# VCU-S02-V00-12VProtection.net
KiCad netlist of a schematic drawn in Altium Designer
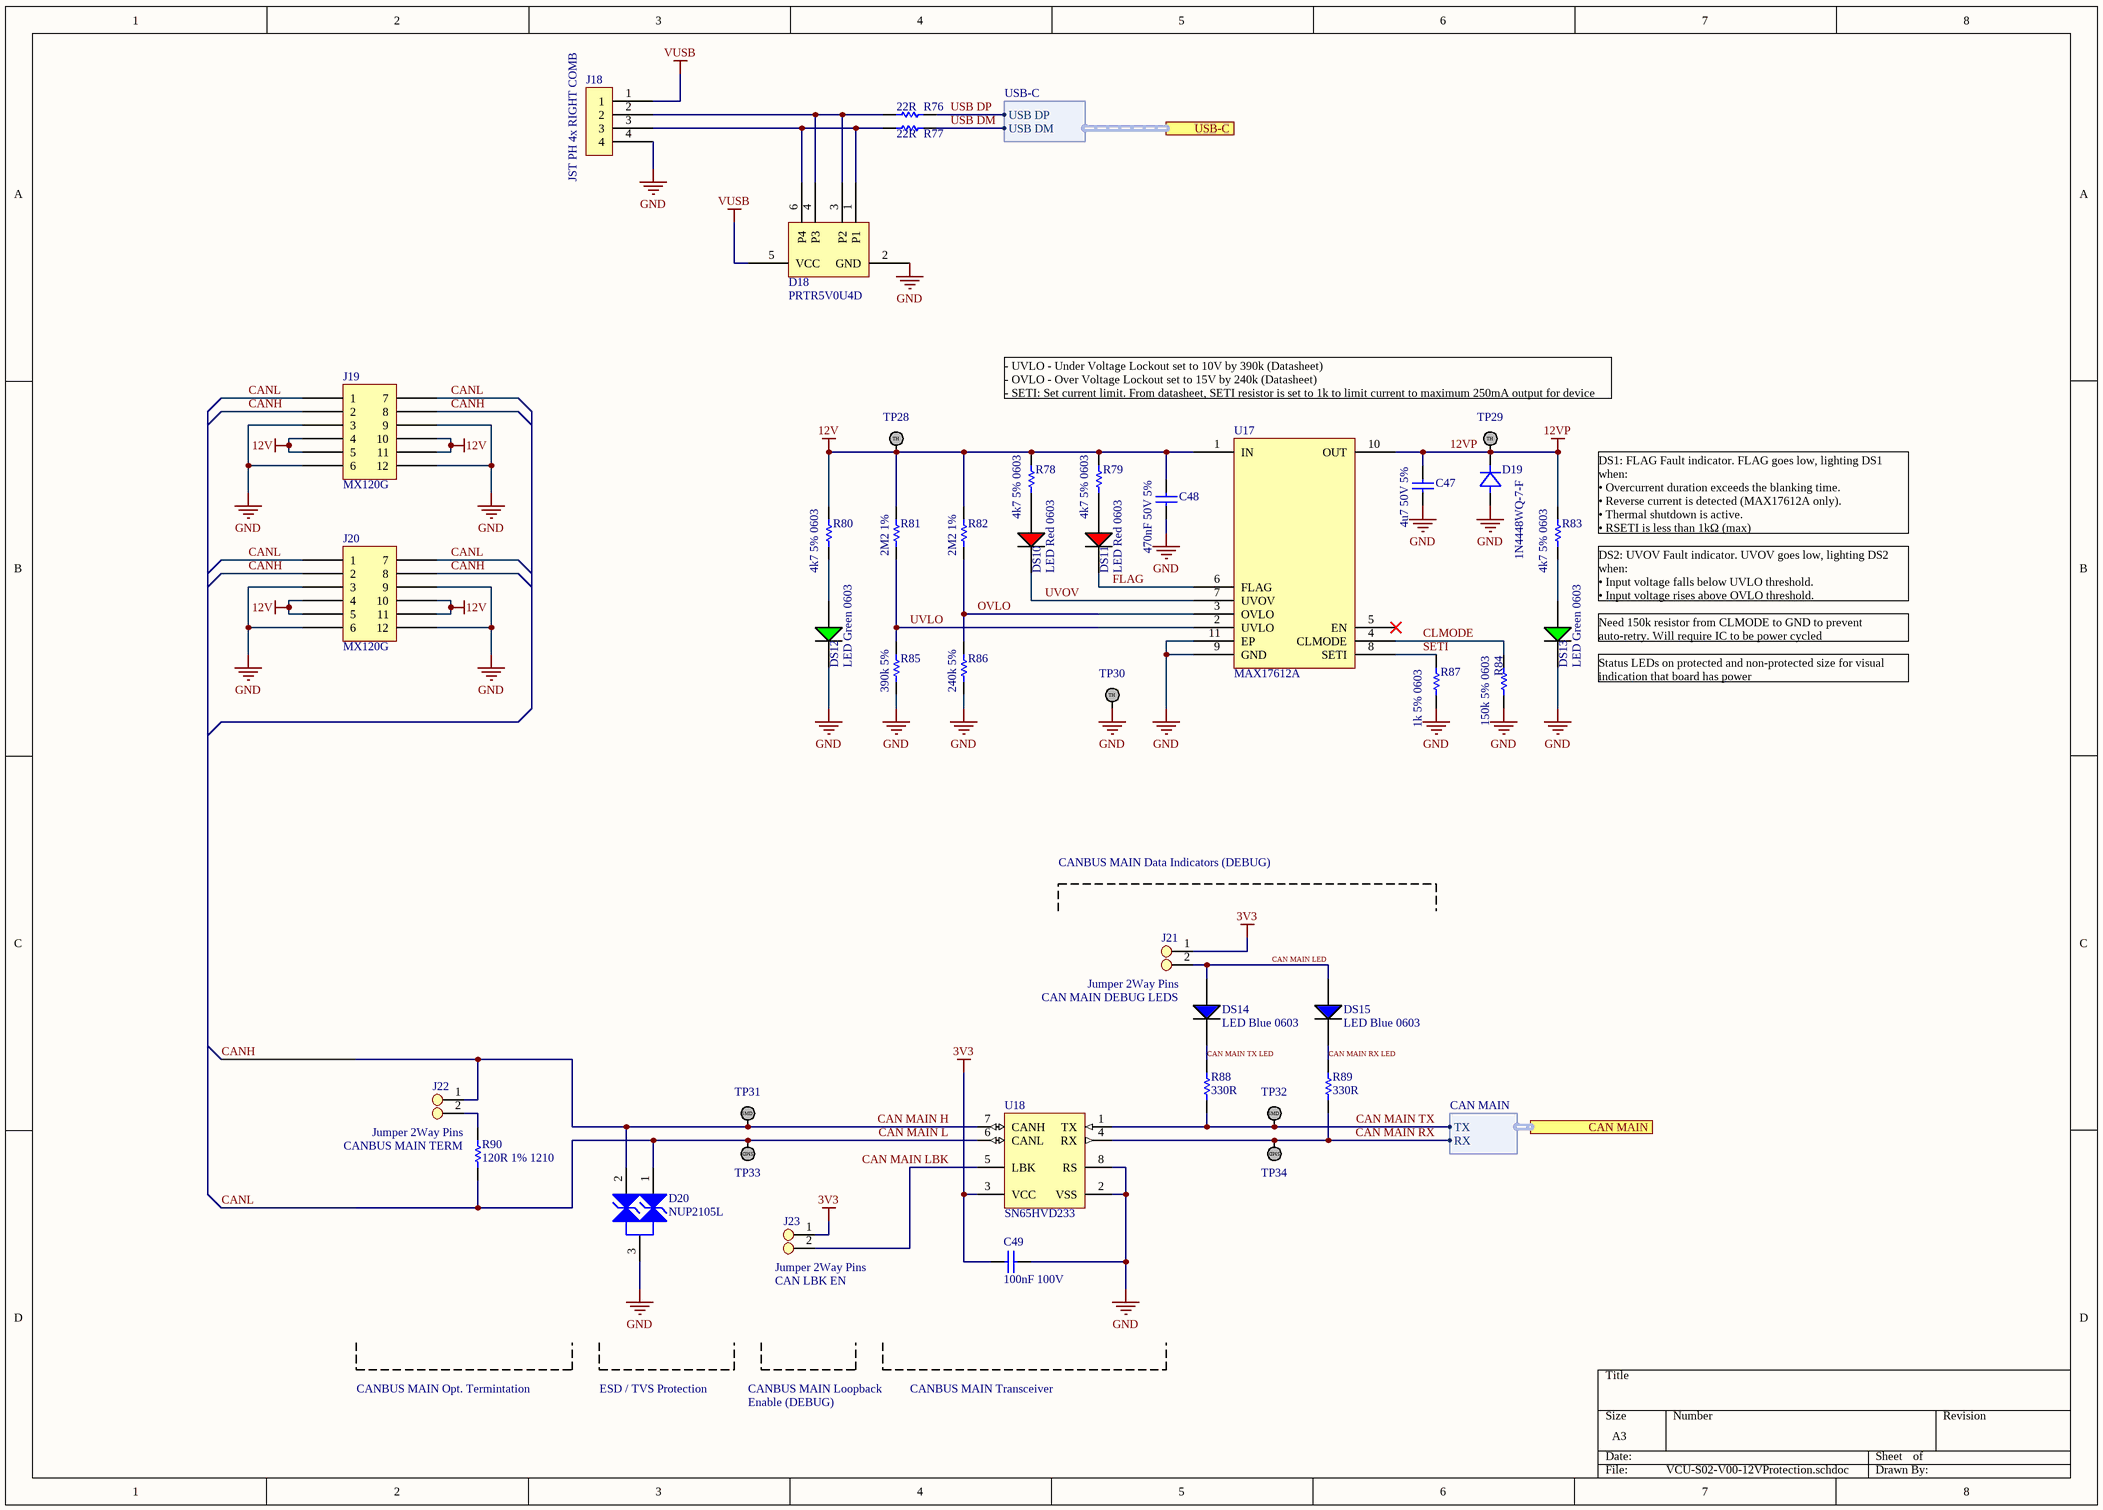
[diagram p0: VCU-S02-V00-12VProtection.schdoc]

(export (version "E")
  (design (tool "Eeschema 10.0.6"))
  (components
    (comp (ref "C47")
      (value "4u7 50V 5%")
      (footprint "Cap_Ceramic_0603")
      (description "Capacitor, Ceramic, SMD, 4u7, 50V, 5%, X7R, 0603")
      (libsource (lib "StandardCapacitors") (part "4u7 50V 5% X7R 0603"))
    )
    (comp (ref "C48")
      (value "470nF 50V 5%")
      (footprint "Cap_Ceramic_0603")
      (description "Capacitor, Ceramic, SMD, 470nF, 50V, 5%, X7R, 0603")
      (libsource (lib "StandardCapacitors") (part "470nF 50V 5% X7R 0603"))
    )
    (comp (ref "C49")
      (value "100nF 100V")
      (footprint "Cap_Ceramic_0603")
      (description "Capacitor, Ceramic, SMD, 100nF, 100V, 5%, X7R, 0603")
      (libsource (lib "StandardCapacitors") (part "100nF 100V 5% X7R 0603"))
    )
    (comp (ref "D18")
      (value "PRTR5V0U4D")
      (footprint "SC-47")
      (description "Clamp Ipp Tvs Diode Surface Mount 6-TSOP")
      (libsource (lib "QUTMS-MCISOLibrary") (part "PRTR5V0U4D"))
    )
    (comp (ref "D19")
      (value "1N4448WQ-7-F")
      (footprint "SMA")
      (description "Diode, SMD, 75V, 5%, 250mA, SOD123")
      (fields
        (field (name "MANUFACTURER") "ON Semiconductor / Fairchild")
        (field (name "MANUFACTURER PART NUMBER") "1N914BWS")
      )
      (libsource (lib "QUTMS_DiodeLibrary") (part "1N4448WQ-7-F"))
    )
    (comp (ref "D20")
      (value "NUP2105L")
      (footprint "NUP2105L")
      (libsource (lib "QUTMS_CANLibrary") (part "NUP2105L"))
    )
    (comp (ref "DS10")
      (value "LED Red 0603")
      (footprint "LED RED 0603")
      (libsource (lib "QUTMS_LEDLibrary") (part "LED Red 0603"))
    )
    (comp (ref "DS11")
      (value "LED Red 0603")
      (footprint "LED RED 0603")
      (libsource (lib "QUTMS_LEDLibrary") (part "LED Red 0603"))
    )
    (comp (ref "DS12")
      (value "LED Green 0603")
      (footprint "LED GREEN 0603")
      (libsource (lib "QUTMS_LEDLibrary") (part "LED Green 0603"))
    )
    (comp (ref "DS13")
      (value "LED Green 0603")
      (footprint "LED GREEN 0603")
      (libsource (lib "QUTMS_LEDLibrary") (part "LED Green 0603"))
    )
    (comp (ref "DS14")
      (value "LED Blue 0603")
      (footprint "LED BLUE 0603")
      (libsource (lib "QUTMS_LEDLibrary") (part "LED BLUE 0603"))
    )
    (comp (ref "DS15")
      (value "LED Blue 0603")
      (footprint "LED BLUE 0603")
      (libsource (lib "QUTMS_LEDLibrary") (part "LED BLUE 0603"))
    )
    (comp (ref "J18")
      (value "JST PH 4x RIGHT COMB")
      (footprint "JST PH 4x RIGHT COMB")
      (libsource (lib "QUTMS-MCISOLibrary") (part "JST PH 4x RIGHT COMB"))
    )
    (comp (ref "J19")
      (value "MX120G")
      (footprint "MX120G")
      (description "MX120G with standard connector layout")
      (libsource (lib "QUTMS_MolexLibrary") (part "MX120G"))
    )
    (comp (ref "J20")
      (value "MX120G")
      (footprint "MX120G")
      (description "MX120G with standard connector layout")
      (libsource (lib "QUTMS_MolexLibrary") (part "MX120G"))
    )
    (comp (ref "J21")
      (value "Jumper 2Way Pins")
      (footprint "Jumper_2Way_Pin")
      (description "Jumper 2Way Side Pins")
      (libsource (lib "QUTMS_JumperLibrary") (part "Jumper 2Way Side Pins"))
    )
    (comp (ref "J22")
      (value "Jumper 2Way Pins")
      (footprint "Jumper_2Way_Pin")
      (description "Jumper 2Way Side Pins")
      (libsource (lib "QUTMS_JumperLibrary") (part "Jumper 2Way Side Pins"))
    )
    (comp (ref "J23")
      (value "Jumper 2Way Pins")
      (footprint "Jumper_2Way_Pin")
      (description "Jumper 2Way Side Pins")
      (libsource (lib "QUTMS_JumperLibrary") (part "Jumper 2Way Side Pins"))
    )
    (comp (ref "R76")
      (value "22R")
      (footprint "Res_ThinFilm_1210")
      (description "Resistor, SMD, 120R, 0.25W, 1%, 1210")
      (libsource (lib "QUTMS-MCISOLibrary") (part "120R 1% 1210"))
    )
    (comp (ref "R77")
      (value "22R")
      (footprint "Res_ThinFilm_1210")
      (description "Resistor, SMD, 120R, 0.25W, 1%, 1210")
      (libsource (lib "QUTMS-MCISOLibrary") (part "120R 1% 1210"))
    )
    (comp (ref "R78")
      (value "4k7 5% 0603")
      (footprint "Res_ThinFilm_0603")
      (description "Resistor, SMD, 4k7, 0.1W, 5%, 0603")
      (libsource (lib "StandardResistors") (part "4k7 5% 0603"))
    )
    (comp (ref "R79")
      (value "4k7 5% 0603")
      (footprint "Res_ThinFilm_0603")
      (description "Resistor, SMD, 4k7, 0.1W, 5%, 0603")
      (libsource (lib "StandardResistors") (part "4k7 5% 0603"))
    )
    (comp (ref "R80")
      (value "4k7 5% 0603")
      (footprint "Res_ThinFilm_0603")
      (description "Resistor, SMD, 4k7, 0.1W, 5%, 0603")
      (libsource (lib "StandardResistors") (part "4k7 5% 0603"))
    )
    (comp (ref "R81")
      (value "2M2 1%")
      (footprint "Res_ThinFilm_0603")
      (description "Resistor, SMD, 2M2, 0.125W, 1%, 0603")
      (libsource (lib "StandardResistors") (part "2M2 1% 0603"))
    )
    (comp (ref "R82")
      (value "2M2 1%")
      (footprint "Res_ThinFilm_0603")
      (description "Resistor, SMD, 2M2, 0.125W, 1%, 0603")
      (libsource (lib "StandardResistors") (part "2M2 1% 0603"))
    )
    (comp (ref "R83")
      (value "4k7 5% 0603")
      (footprint "Res_ThinFilm_0603")
      (description "Resistor, SMD, 4k7, 0.1W, 5%, 0603")
      (libsource (lib "StandardResistors") (part "4k7 5% 0603"))
    )
    (comp (ref "R84")
      (value "150k 5% 0603")
      (footprint "Res_ThinFilm_0603")
      (description "Resistor, SMD, 150k, 0.1W, 5%, 0603")
      (libsource (lib "StandardResistors") (part "150k 5%, 0603"))
    )
    (comp (ref "R85")
      (value "390k 5%")
      (footprint "Res_ThinFilm_0603")
      (description "Resistor, SMD, 390k, 0.1W, 5%, 0603")
      (libsource (lib "StandardResistors") (part "390k 5% 0603"))
    )
    (comp (ref "R86")
      (value "240k 5%")
      (footprint "Res_ThinFilm_0603")
      (description "Resistor, SMD, 240k, 0.1W, 5%, 0603")
      (libsource (lib "StandardResistors") (part "240k 5% 0603"))
    )
    (comp (ref "R87")
      (value "1k 5% 0603")
      (footprint "Res_ThinFilm_0603")
      (description "Resistor, SMD, 1k, 0.1W, 5%, 0603")
      (libsource (lib "StandardResistors") (part "1k 5% 0603"))
    )
    (comp (ref "R88")
      (value "330R")
      (footprint "Res_ThinFilm_0603")
      (description "Resistor, SMD, 330R, 0.1W, 5%, 0603")
      (libsource (lib "StandardResistors") (part "330R 5% 0603"))
    )
    (comp (ref "R89")
      (value "330R")
      (footprint "Res_ThinFilm_0603")
      (description "Resistor, SMD, 330R, 0.1W, 5%, 0603")
      (libsource (lib "StandardResistors") (part "330R 5% 0603"))
    )
    (comp (ref "R90")
      (value "120R 1% 1210")
      (footprint "Res_ThinFilm_1210")
      (description "Resistor, SMD, 120R, 0.25W, 1%, 1210")
      (libsource (lib "StandardResistors") (part "120R 1% 1210"))
    )
    (comp (ref "TP28")
      (value "TestPoint")
      (footprint "TestPoint")
      (libsource (lib "StandardTest") (part "TestPoint"))
    )
    (comp (ref "TP29")
      (value "TestPoint")
      (footprint "TestPoint")
      (libsource (lib "StandardTest") (part "TestPoint"))
    )
    (comp (ref "TP30")
      (value "TestPoint")
      (footprint "TestPoint")
      (libsource (lib "StandardTest") (part "TestPoint"))
    )
    (comp (ref "TP31")
      (value "TestPoint_SMD")
      (footprint "TestPointSMD")
      (libsource (lib "StandardTest") (part "TestPoint_SMD"))
    )
    (comp (ref "TP32")
      (value "TestPoint_SMD")
      (footprint "TestPointSMD")
      (libsource (lib "StandardTest") (part "TestPoint_SMD"))
    )
    (comp (ref "TP33")
      (value "TestPoint_SMD")
      (footprint "TestPointSMD")
      (libsource (lib "StandardTest") (part "TestPoint_SMD"))
    )
    (comp (ref "TP34")
      (value "TestPoint_SMD")
      (footprint "TestPointSMD")
      (libsource (lib "StandardTest") (part "TestPoint_SMD"))
    )
    (comp (ref "U17")
      (value "MAX17612A")
      (footprint "10-Pin TDFN EP")
      (description "4.5V to 60V, 250mA Current-Limiter with OV, UV, and Reverse Protection")
      (libsource (lib "QUTMS_IntegratedCircuitLibrary") (part "MAX17612A"))
    )
    (comp (ref "U18")
      (value "SN65HVD233")
      (footprint "SN65HVD233DR")
      (libsource (lib "QUTMS_CANLibrary") (part "SN65HVD233"))
    )
  )
  (nets
    (net (code "4") (name "/CAN MAIN H") (class "Default")
      (node (ref "D20") (pin "2") (pinfunction "2_2") (pintype "passive"))
      (node (ref "J19") (pin "2") (pinfunction "2_2") (pintype "passive"))
      (node (ref "J19") (pin "8") (pinfunction "8_8") (pintype "passive"))
      (node (ref "J20") (pin "2") (pinfunction "2_2") (pintype "passive"))
      (node (ref "J20") (pin "8") (pinfunction "8_8") (pintype "passive"))
      (node (ref "J22") (pin "1") (pinfunction "1_1") (pintype "passive"))
      (node (ref "TP31") (pin "1") (pinfunction "1_1") (pintype "passive"))
      (node (ref "U18") (pin "7") (pinfunction "CANH_7") (pintype "bidirectional"))
    )
    (net (code "5") (name "/CAN MAIN L") (class "Default")
      (node (ref "D20") (pin "1") (pinfunction "1_1") (pintype "passive"))
      (node (ref "J19") (pin "1") (pinfunction "1_1") (pintype "passive"))
      (node (ref "J19") (pin "7") (pinfunction "7_7") (pintype "passive"))
      (node (ref "J20") (pin "1") (pinfunction "1_1") (pintype "passive"))
      (node (ref "J20") (pin "7") (pinfunction "7_7") (pintype "passive"))
      (node (ref "R90") (pin "1") (pinfunction "1_1") (pintype "passive"))
      (node (ref "TP33") (pin "1") (pinfunction "1_1") (pintype "passive"))
      (node (ref "U18") (pin "6") (pinfunction "CANL_6") (pintype "bidirectional"))
    )
    (net (code "6") (name "/CAN MAIN LBK") (class "Default")
      (node (ref "J23") (pin "2") (pinfunction "2_2") (pintype "passive"))
      (node (ref "U18") (pin "5") (pinfunction "LBK_5") (pintype "passive"))
    )
    (net (code "7") (name "/CAN MAIN LED") (class "Default")
      (node (ref "DS14") (pin "1") (pinfunction "A_1") (pintype "passive"))
      (node (ref "DS15") (pin "1") (pinfunction "A_1") (pintype "passive"))
      (node (ref "J21") (pin "2") (pinfunction "2_2") (pintype "passive"))
    )
    (net (code "8") (name "/CAN MAIN RX") (class "Default")
      (node (ref "R89") (pin "1") (pinfunction "1_1") (pintype "passive"))
      (node (ref "TP34") (pin "1") (pinfunction "1_1") (pintype "passive"))
      (node (ref "U18") (pin "4") (pinfunction "RX_4") (pintype "output"))
    )
    (net (code "9") (name "/CAN MAIN RX LED") (class "Default")
      (node (ref "DS15") (pin "2") (pinfunction "C_2") (pintype "passive"))
      (node (ref "R89") (pin "2") (pinfunction "2_2") (pintype "passive"))
    )
    (net (code "10") (name "/CAN MAIN TX") (class "Default")
      (node (ref "R88") (pin "1") (pinfunction "1_1") (pintype "passive"))
      (node (ref "TP32") (pin "1") (pinfunction "1_1") (pintype "passive"))
      (node (ref "U18") (pin "1") (pinfunction "TX_1") (pintype "input"))
    )
    (net (code "11") (name "/CAN MAIN TX LED") (class "Default")
      (node (ref "DS14") (pin "2") (pinfunction "C_2") (pintype "passive"))
      (node (ref "R88") (pin "2") (pinfunction "2_2") (pintype "passive"))
    )
    (net (code "12") (name "/CLMODE") (class "Default")
      (node (ref "R84") (pin "2") (pinfunction "2_2") (pintype "passive"))
      (node (ref "U17") (pin "4") (pinfunction "CLMODE_4") (pintype "passive"))
    )
    (net (code "13") (name "/FLAG") (class "Default")
      (node (ref "DS11") (pin "2") (pinfunction "C_2") (pintype "passive"))
      (node (ref "U17") (pin "6") (pinfunction "FLAG_6") (pintype "passive"))
    )
    (net (code "14") (name "/OVLO") (class "Default")
      (node (ref "R82") (pin "1") (pinfunction "1_1") (pintype "passive"))
      (node (ref "R86") (pin "2") (pinfunction "2_2") (pintype "passive"))
      (node (ref "U17") (pin "3") (pinfunction "OVLO_3") (pintype "passive"))
    )
    (net (code "15") (name "/SETI") (class "Default")
      (node (ref "R87") (pin "2") (pinfunction "2_2") (pintype "passive"))
      (node (ref "U17") (pin "8") (pinfunction "SETI_8") (pintype "passive"))
    )
    (net (code "16") (name "/USB DM") (class "Default")
      (node (ref "R77") (pin "2") (pinfunction "2_2") (pintype "passive"))
    )
    (net (code "17") (name "/USB DP") (class "Default")
      (node (ref "R76") (pin "2") (pinfunction "2_2") (pintype "passive"))
    )
    (net (code "18") (name "/UVLO") (class "Default")
      (node (ref "R81") (pin "1") (pinfunction "1_1") (pintype "passive"))
      (node (ref "R85") (pin "2") (pinfunction "2_2") (pintype "passive"))
      (node (ref "U17") (pin "2") (pinfunction "UVLO_2") (pintype "passive"))
    )
    (net (code "19") (name "/UVOV") (class "Default")
      (node (ref "DS10") (pin "2") (pinfunction "C_2") (pintype "passive"))
      (node (ref "U17") (pin "7") (pinfunction "UVOV_7") (pintype "passive"))
    )
    (net (code "22") (name "3V3") (class "Default")
      (node (ref "C49") (pin "2") (pinfunction "2_2") (pintype "passive"))
      (node (ref "J21") (pin "1") (pinfunction "1_1") (pintype "passive"))
      (node (ref "J23") (pin "1") (pinfunction "1_1") (pintype "passive"))
      (node (ref "U18") (pin "3") (pinfunction "VCC_3") (pintype "passive"))
    )
    (net (code "23") (name "12V") (class "Default")
      (node (ref "C48") (pin "2") (pinfunction "2_2") (pintype "passive"))
      (node (ref "J19") (pin "10") (pinfunction "10_10") (pintype "passive"))
      (node (ref "J19") (pin "11") (pinfunction "11_11") (pintype "passive"))
      (node (ref "J19") (pin "4") (pinfunction "4_4") (pintype "passive"))
      (node (ref "J19") (pin "5") (pinfunction "5_5") (pintype "passive"))
      (node (ref "J20") (pin "10") (pinfunction "10_10") (pintype "passive"))
      (node (ref "J20") (pin "11") (pinfunction "11_11") (pintype "passive"))
      (node (ref "J20") (pin "4") (pinfunction "4_4") (pintype "passive"))
      (node (ref "J20") (pin "5") (pinfunction "5_5") (pintype "passive"))
      (node (ref "R78") (pin "2") (pinfunction "2_2") (pintype "passive"))
      (node (ref "R79") (pin "2") (pinfunction "2_2") (pintype "passive"))
      (node (ref "R80") (pin "2") (pinfunction "2_2") (pintype "passive"))
      (node (ref "R81") (pin "2") (pinfunction "2_2") (pintype "passive"))
      (node (ref "R82") (pin "2") (pinfunction "2_2") (pintype "passive"))
      (node (ref "TP28") (pin "1") (pinfunction "1_1") (pintype "passive"))
      (node (ref "U17") (pin "1") (pinfunction "IN_1") (pintype "passive"))
    )
    (net (code "24") (name "12VP") (class "Default")
      (node (ref "C47") (pin "2") (pinfunction "2_2") (pintype "passive"))
      (node (ref "D19") (pin "K") (pinfunction "Cathode_K") (pintype "passive"))
      (node (ref "R83") (pin "2") (pinfunction "2_2") (pintype "passive"))
      (node (ref "TP29") (pin "1") (pinfunction "1_1") (pintype "passive"))
      (node (ref "U17") (pin "10") (pinfunction "OUT_10") (pintype "passive"))
    )
    (net (code "25") (name "GND") (class "Default")
      (node (ref "C47") (pin "1") (pinfunction "1_1") (pintype "passive"))
      (node (ref "C48") (pin "1") (pinfunction "1_1") (pintype "passive"))
      (node (ref "C49") (pin "1") (pinfunction "1_1") (pintype "passive"))
      (node (ref "D18") (pin "2") (pinfunction "GND_2") (pintype "passive"))
      (node (ref "D19") (pin "A") (pinfunction "Anode_A") (pintype "passive"))
      (node (ref "D20") (pin "3") (pinfunction "3_3") (pintype "passive"))
      (node (ref "DS12") (pin "2") (pinfunction "C_2") (pintype "passive"))
      (node (ref "DS13") (pin "2") (pinfunction "C_2") (pintype "passive"))
      (node (ref "J18") (pin "4") (pinfunction "4_4") (pintype "passive"))
      (node (ref "J19") (pin "12") (pinfunction "12_12") (pintype "passive"))
      (node (ref "J19") (pin "3") (pinfunction "3_3") (pintype "passive"))
      (node (ref "J19") (pin "6") (pinfunction "6_6") (pintype "passive"))
      (node (ref "J19") (pin "9") (pinfunction "9_9") (pintype "passive"))
      (node (ref "J20") (pin "12") (pinfunction "12_12") (pintype "passive"))
      (node (ref "J20") (pin "3") (pinfunction "3_3") (pintype "passive"))
      (node (ref "J20") (pin "6") (pinfunction "6_6") (pintype "passive"))
      (node (ref "J20") (pin "9") (pinfunction "9_9") (pintype "passive"))
      (node (ref "R84") (pin "1") (pinfunction "1_1") (pintype "passive"))
      (node (ref "R85") (pin "1") (pinfunction "1_1") (pintype "passive"))
      (node (ref "R86") (pin "1") (pinfunction "1_1") (pintype "passive"))
      (node (ref "R87") (pin "1") (pinfunction "1_1") (pintype "passive"))
      (node (ref "TP30") (pin "1") (pinfunction "1_1") (pintype "passive"))
      (node (ref "U17") (pin "11") (pinfunction "EP_11") (pintype "passive"))
      (node (ref "U17") (pin "9") (pinfunction "GND_9") (pintype "passive"))
      (node (ref "U18") (pin "2") (pinfunction "VSS_2") (pintype "passive"))
      (node (ref "U18") (pin "8") (pinfunction "RS_8") (pintype "passive"))
    )
    (net (code "26") (name "Net-(D18-P1)") (class "Default")
      (node (ref "D18") (pin "1") (pinfunction "P1_1") (pintype "passive"))
      (node (ref "D18") (pin "6") (pinfunction "P4_6") (pintype "passive"))
      (node (ref "J18") (pin "3") (pinfunction "3_3") (pintype "passive"))
      (node (ref "R77") (pin "1") (pinfunction "1_1") (pintype "passive"))
    )
    (net (code "27") (name "Net-(D18-P2)") (class "Default")
      (node (ref "D18") (pin "3") (pinfunction "P2_3") (pintype "passive"))
      (node (ref "D18") (pin "4") (pinfunction "P3_4") (pintype "passive"))
      (node (ref "J18") (pin "2") (pinfunction "2_2") (pintype "passive"))
      (node (ref "R76") (pin "1") (pinfunction "1_1") (pintype "passive"))
    )
    (net (code "28") (name "Net-(DS10-A)") (class "Default")
      (node (ref "DS10") (pin "1") (pinfunction "A_1") (pintype "passive"))
      (node (ref "R78") (pin "1") (pinfunction "1_1") (pintype "passive"))
    )
    (net (code "29") (name "Net-(DS11-A)") (class "Default")
      (node (ref "DS11") (pin "1") (pinfunction "A_1") (pintype "passive"))
      (node (ref "R79") (pin "1") (pinfunction "1_1") (pintype "passive"))
    )
    (net (code "30") (name "Net-(DS12-A)") (class "Default")
      (node (ref "DS12") (pin "1") (pinfunction "A_1") (pintype "passive"))
      (node (ref "R80") (pin "1") (pinfunction "1_1") (pintype "passive"))
    )
    (net (code "31") (name "Net-(DS13-A)") (class "Default")
      (node (ref "DS13") (pin "1") (pinfunction "A_1") (pintype "passive"))
      (node (ref "R83") (pin "1") (pinfunction "1_1") (pintype "passive"))
    )
    (net (code "32") (name "Net-(J22-Pad2)") (class "Default")
      (node (ref "J22") (pin "2") (pinfunction "2_2") (pintype "passive"))
      (node (ref "R90") (pin "2") (pinfunction "2_2") (pintype "passive"))
    )
    (net (code "33") (name "VUSB") (class "Default")
      (node (ref "D18") (pin "5") (pinfunction "VCC_5") (pintype "passive"))
      (node (ref "J18") (pin "1") (pinfunction "1_1") (pintype "passive"))
    )
    (net (code "34") (name "unconnected-(U17-EN-Pad5)") (class "Default")
      (node (ref "U17") (pin "5") (pinfunction "EN_5") (pintype "passive+no_connect"))
    )
  )
)
